# Smart_System.net
KiCad netlist of a schematic drawn in EasyEDA Pro
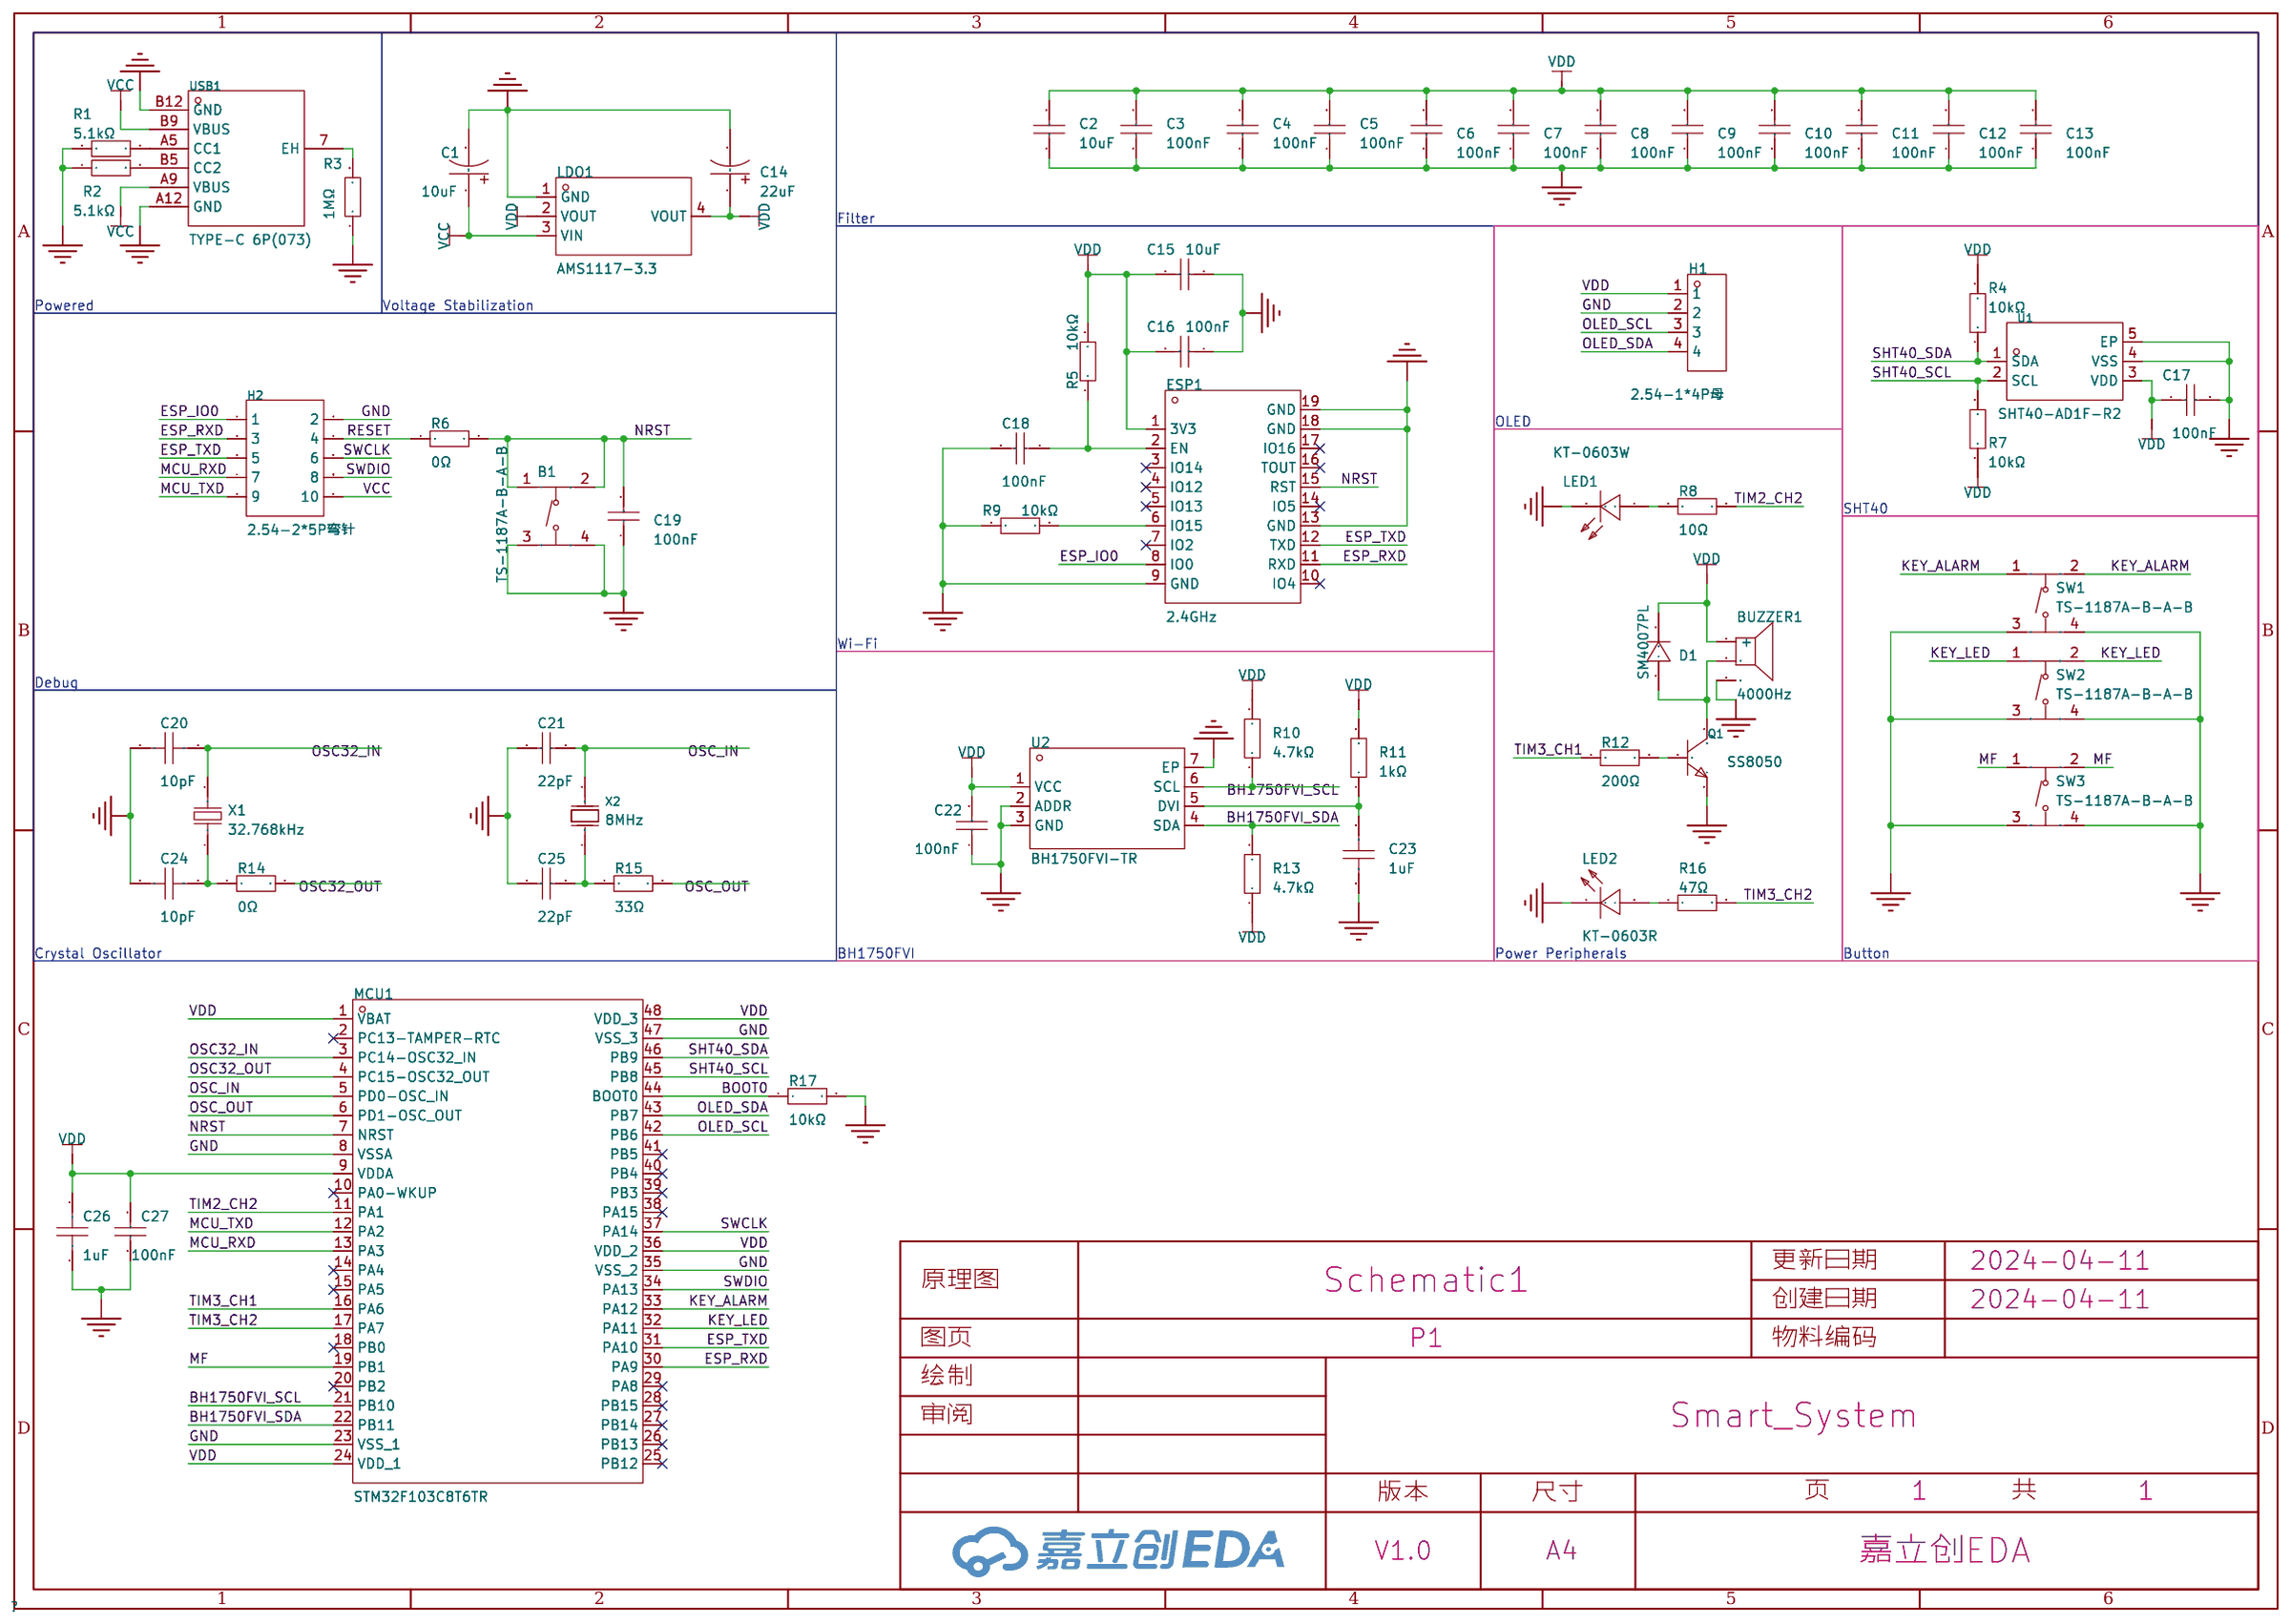
[diagram p0: schematic sheet]

(export (version "E")
  (design (tool "Eeschema 10.0.6"))
  (components
    (comp (ref "B1")
      (value "TS-1187A-B-A-B")
      (footprint "easyedapro:SW-SMD_4P-L5.1-W5.1-P3.70-LS6.5-TL-2")
      (description "触点电流:50mA;额定电压(DC):12V;绝缘电阻:-;电路结构:单刀单掷;安装方式:立贴;带灯:无;作用力:160gf;机械寿命:10万次;带支架:否;")
      (fields (field (name "Manufacturer") "XKB Connectivity(中国星坤)"))
      (libsource (lib "easyedapro") (part "TS-1187A-B-A-B"))
    )
    (comp (ref "BUZZER1")
      (value "4000Hz")
      (footprint "easyedapro:BUZ-SMD_FST-5018")
      (fields (field (name "Manufacturer Part") "FUET-5018") (field (name "Manufacturer") "FUET(福声科技)"))
      (libsource (lib "easyedapro") (part "FST-5018"))
    )
    (comp (ref "C1")
      (value "10uF")
      (footprint "easyedapro:CAP-SMD_BD3.0-L3.3-W3.3-FD")
      (description "容值:10uF;精度:±20%;额定电压:16V;纹波电流:-;等效串联电阻:-;")
      (fields (field (name "Manufacturer Part") "VE-100M1CTR-0305") (field (name "Manufacturer") "lelon(立隆)"))
      (libsource (lib "easyedapro") (part "VE-100M1C0305-TRO"))
    )
    (comp (ref "C2")
      (value "10uF")
      (footprint "easyedapro:C0402")
      (description "容值:10uF;精度:±20%;额定电压:6.3V;材质(温度系数):X5R;")
      (fields
        (field (name "Manufacturer Part") "CL05A106MQ5NUNC")
        (field (name "Manufacturer") "SAMSUNG(三星)")
      )
      (libsource (lib "easyedapro") (part "CL05A106MQ5NUNC"))
    )
    (comp (ref "C3")
      (value "100nF")
      (footprint "easyedapro:C0402")
      (description "容值:100nF;精度:±10%;额定电压:16V;材质(温度系数):X7R;")
      (fields
        (field (name "Manufacturer Part") "CL05B104KO5NNNC")
        (field (name "Manufacturer") "SAMSUNG(三星)")
      )
      (libsource (lib "easyedapro") (part "CL05B104KO5NNNC"))
    )
    (comp (ref "C4")
      (value "100nF")
      (footprint "easyedapro:C0402")
      (description "容值:100nF;精度:±10%;额定电压:16V;材质(温度系数):X7R;")
      (fields
        (field (name "Manufacturer Part") "CL05B104KO5NNNC")
        (field (name "Manufacturer") "SAMSUNG(三星)")
      )
      (libsource (lib "easyedapro") (part "CL05B104KO5NNNC"))
    )
    (comp (ref "C5")
      (value "100nF")
      (footprint "easyedapro:C0402")
      (description "容值:100nF;精度:±10%;额定电压:16V;材质(温度系数):X7R;")
      (fields
        (field (name "Manufacturer Part") "CL05B104KO5NNNC")
        (field (name "Manufacturer") "SAMSUNG(三星)")
      )
      (libsource (lib "easyedapro") (part "CL05B104KO5NNNC"))
    )
    (comp (ref "C6")
      (value "100nF")
      (footprint "easyedapro:C0402")
      (description "容值:100nF;精度:±10%;额定电压:16V;材质(温度系数):X7R;")
      (fields
        (field (name "Manufacturer Part") "CL05B104KO5NNNC")
        (field (name "Manufacturer") "SAMSUNG(三星)")
      )
      (libsource (lib "easyedapro") (part "CL05B104KO5NNNC"))
    )
    (comp (ref "C7")
      (value "100nF")
      (footprint "easyedapro:C0402")
      (description "容值:100nF;精度:±10%;额定电压:16V;材质(温度系数):X7R;")
      (fields
        (field (name "Manufacturer Part") "CL05B104KO5NNNC")
        (field (name "Manufacturer") "SAMSUNG(三星)")
      )
      (libsource (lib "easyedapro") (part "CL05B104KO5NNNC"))
    )
    (comp (ref "C8")
      (value "100nF")
      (footprint "easyedapro:C0402")
      (description "容值:100nF;精度:±10%;额定电压:16V;材质(温度系数):X7R;")
      (fields
        (field (name "Manufacturer Part") "CL05B104KO5NNNC")
        (field (name "Manufacturer") "SAMSUNG(三星)")
      )
      (libsource (lib "easyedapro") (part "CL05B104KO5NNNC"))
    )
    (comp (ref "C9")
      (value "100nF")
      (footprint "easyedapro:C0402")
      (description "容值:100nF;精度:±10%;额定电压:16V;材质(温度系数):X7R;")
      (fields
        (field (name "Manufacturer Part") "CL05B104KO5NNNC")
        (field (name "Manufacturer") "SAMSUNG(三星)")
      )
      (libsource (lib "easyedapro") (part "CL05B104KO5NNNC"))
    )
    (comp (ref "C10")
      (value "100nF")
      (footprint "easyedapro:C0402")
      (description "容值:100nF;精度:±10%;额定电压:16V;材质(温度系数):X7R;")
      (fields
        (field (name "Manufacturer Part") "CL05B104KO5NNNC")
        (field (name "Manufacturer") "SAMSUNG(三星)")
      )
      (libsource (lib "easyedapro") (part "CL05B104KO5NNNC"))
    )
    (comp (ref "C11")
      (value "100nF")
      (footprint "easyedapro:C0402")
      (description "容值:100nF;精度:±10%;额定电压:16V;材质(温度系数):X7R;")
      (fields
        (field (name "Manufacturer Part") "CL05B104KO5NNNC")
        (field (name "Manufacturer") "SAMSUNG(三星)")
      )
      (libsource (lib "easyedapro") (part "CL05B104KO5NNNC"))
    )
    (comp (ref "C12")
      (value "100nF")
      (footprint "easyedapro:C0402")
      (description "容值:100nF;精度:±10%;额定电压:16V;材质(温度系数):X7R;")
      (fields
        (field (name "Manufacturer Part") "CL05B104KO5NNNC")
        (field (name "Manufacturer") "SAMSUNG(三星)")
      )
      (libsource (lib "easyedapro") (part "CL05B104KO5NNNC"))
    )
    (comp (ref "C13")
      (value "100nF")
      (footprint "easyedapro:C0402")
      (description "容值:100nF;精度:±10%;额定电压:16V;材质(温度系数):X7R;")
      (fields
        (field (name "Manufacturer Part") "CL05B104KO5NNNC")
        (field (name "Manufacturer") "SAMSUNG(三星)")
      )
      (libsource (lib "easyedapro") (part "CL05B104KO5NNNC"))
    )
    (comp (ref "C14")
      (value "22uF")
      (footprint "easyedapro:CAP-SMD_BD3.0-L3.3-W3.3-FD")
      (description "容值:22uF;精度:±20%;额定电压:10V;纹波电流:-;等效串联电阻:-;")
      (fields (field (name "Manufacturer Part") "VE-220M1ATR-0305") (field (name "Manufacturer") "lelon(立隆)"))
      (libsource (lib "easyedapro") (part "VE-220M1A0305-TRO"))
    )
    (comp (ref "C15")
      (value "10uF")
      (footprint "easyedapro:C0402")
      (description "容值:10uF;精度:±20%;额定电压:6.3V;材质(温度系数):X5R;")
      (fields
        (field (name "Manufacturer Part") "CL05A106MQ5NUNC")
        (field (name "Manufacturer") "SAMSUNG(三星)")
      )
      (libsource (lib "easyedapro") (part "CL05A106MQ5NUNC"))
    )
    (comp (ref "C16")
      (value "100nF")
      (footprint "easyedapro:C0402")
      (description "容值:100nF;精度:±10%;额定电压:16V;材质(温度系数):X7R;")
      (fields
        (field (name "Manufacturer Part") "CL05B104KO5NNNC")
        (field (name "Manufacturer") "SAMSUNG(三星)")
      )
      (libsource (lib "easyedapro") (part "CL05B104KO5NNNC"))
    )
    (comp (ref "C17")
      (value "100nF")
      (footprint "easyedapro:C0402")
      (description "容值:100nF;精度:±10%;额定电压:16V;材质(温度系数):X7R;")
      (fields
        (field (name "Manufacturer Part") "CL05B104KO5NNNC")
        (field (name "Manufacturer") "SAMSUNG(三星)")
      )
      (libsource (lib "easyedapro") (part "CL05B104KO5NNNC"))
    )
    (comp (ref "C18")
      (value "100nF")
      (footprint "easyedapro:C0402")
      (description "容值:100nF;精度:±10%;额定电压:16V;材质(温度系数):X7R;")
      (fields
        (field (name "Manufacturer Part") "CL05B104KO5NNNC")
        (field (name "Manufacturer") "SAMSUNG(三星)")
      )
      (libsource (lib "easyedapro") (part "CL05B104KO5NNNC"))
    )
    (comp (ref "C19")
      (value "100nF")
      (footprint "easyedapro:C0402")
      (description "容值:100nF;精度:±10%;额定电压:16V;材质(温度系数):X7R;")
      (fields
        (field (name "Manufacturer Part") "CL05B104KO5NNNC")
        (field (name "Manufacturer") "SAMSUNG(三星)")
      )
      (libsource (lib "easyedapro") (part "CL05B104KO5NNNC"))
    )
    (comp (ref "C20")
      (value "10pF")
      (footprint "easyedapro:C0402")
      (description "容值:10pF;精度:±5%;额定电压:50V;材质(温度系数):C0G;")
      (fields
        (field (name "Manufacturer Part") "CL05C100JB5NNNC")
        (field (name "Manufacturer") "SAMSUNG(三星)")
      )
      (libsource (lib "easyedapro") (part "CL05C100JB5NNNC"))
    )
    (comp (ref "C21")
      (value "22pF")
      (footprint "easyedapro:C0402")
      (description "容值:22pF;精度:±5%;额定电压:50V;材质(温度系数):C0G;")
      (fields (field (name "Manufacturer Part") "0402CG220J500NT") (field (name "Manufacturer") "FH(风华)"))
      (libsource (lib "easyedapro") (part "0402CG220J500NT"))
    )
    (comp (ref "C22")
      (value "100nF")
      (footprint "easyedapro:C0402")
      (description "容值:100nF;精度:±10%;额定电压:16V;材质(温度系数):X7R;")
      (fields
        (field (name "Manufacturer Part") "CL05B104KO5NNNC")
        (field (name "Manufacturer") "SAMSUNG(三星)")
      )
      (libsource (lib "easyedapro") (part "CL05B104KO5NNNC"))
    )
    (comp (ref "C23")
      (value "1uF")
      (footprint "easyedapro:C0402")
      (description "容值:1uF;精度:±10%;额定电压:25V;材质(温度系数):X5R;")
      (fields
        (field (name "Manufacturer Part") "CL05A105KA5NQNC")
        (field (name "Manufacturer") "SAMSUNG(三星)")
      )
      (libsource (lib "easyedapro") (part "CL05A105KA5NQNC"))
    )
    (comp (ref "C24")
      (value "10pF")
      (footprint "easyedapro:C0402")
      (description "容值:10pF;精度:±5%;额定电压:50V;材质(温度系数):C0G;")
      (fields
        (field (name "Manufacturer Part") "CL05C100JB5NNNC")
        (field (name "Manufacturer") "SAMSUNG(三星)")
      )
      (libsource (lib "easyedapro") (part "CL05C100JB5NNNC"))
    )
    (comp (ref "C25")
      (value "22pF")
      (footprint "easyedapro:C0402")
      (description "容值:22pF;精度:±5%;额定电压:50V;材质(温度系数):C0G;")
      (fields (field (name "Manufacturer Part") "0402CG220J500NT") (field (name "Manufacturer") "FH(风华)"))
      (libsource (lib "easyedapro") (part "0402CG220J500NT"))
    )
    (comp (ref "C26")
      (value "1uF")
      (footprint "easyedapro:C0402")
      (description "容值:1uF;精度:±10%;额定电压:25V;材质(温度系数):X5R;")
      (fields
        (field (name "Manufacturer Part") "CL05A105KA5NQNC")
        (field (name "Manufacturer") "SAMSUNG(三星)")
      )
      (libsource (lib "easyedapro") (part "CL05A105KA5NQNC"))
    )
    (comp (ref "C27")
      (value "100nF")
      (footprint "easyedapro:C0402")
      (description "容值:100nF;精度:±10%;额定电压:16V;材质(温度系数):X7R;")
      (fields
        (field (name "Manufacturer Part") "CL05B104KO5NNNC")
        (field (name "Manufacturer") "SAMSUNG(三星)")
      )
      (libsource (lib "easyedapro") (part "CL05B104KO5NNNC"))
    )
    (comp (ref "D1")
      (value "SM4007PL")
      (footprint "easyedapro:SOD-123F_L2.8-W1.8-LS3.7-RD")
      (description "二极管配置:-;正向压降(Vf):1.1V@1A;直流反向耐压(Vr):1kV;平均整流电流(Io):1A;")
      (fields (field (name "Manufacturer") "MDD"))
      (libsource (lib "easyedapro") (part "SM4007PL"))
    )
    (comp (ref "ESP1")
      (value "2.4GHz")
      (footprint "easyedapro:WIFIM-SMD_18P-L18.0-W20.0-P1.50")
      (description "频率:2.4GHz;发射功率:20.5dBm;核心处理器:ESP8266EX;")
      (fields
        (field (name "Manufacturer Part") "ESP-WROOM-02-N4")
        (field (name "Manufacturer") "ESPRESSIF(乐鑫)")
      )
      (libsource (lib "easyedapro") (part "ESP-WROOM-02(4MB)"))
    )
    (comp (ref "H1")
      (value "2.54-1*4P母")
      (footprint "easyedapro:HDR-TH_4P-P2.54-V-F")
      (fields (field (name "Manufacturer") "BOOMELE(博穆精密)"))
      (libsource (lib "easyedapro") (part "2.54-1*4P母"))
    )
    (comp (ref "H2")
      (value "2.54-2*5P弯针")
      (footprint "easyedapro:HDR-TH_10P-P2.54-H-M-R2-C5-S2.54-W12.9")
      (fields (field (name "Manufacturer") "BOOMELE(博穆精密)"))
      (libsource (lib "easyedapro") (part "2*5P header"))
    )
    (comp (ref "LDO1")
      (value "AMS1117-3.3")
      (footprint "easyedapro:SOT-223-3_L6.5-W3.4-P2.30-LS7.0-BR")
      (description "输出类型:固定;输出极性:正;最大输入电压:-;输出电压:3.3V;输出电流:1A;电源纹波抑制比(PSRR):72dB@(120Hz);")
      (fields (field (name "Manufacturer") "AMS"))
      (libsource (lib "easyedapro") (part "AMS1117-3.3"))
    )
    (comp (ref "LED1")
      (value "KT-0603W")
      (footprint "easyedapro:LED0603-R-RD_WHITE")
      (description "发光颜色:白色;")
      (fields (field (name "Manufacturer") "KENTO"))
      (libsource (lib "easyedapro") (part "0603White light_C2290"))
    )
    (comp (ref "LED2")
      (value "KT-0603R")
      (footprint "easyedapro:LED0603-RD")
      (description "发光颜色:红灯;二极管配置:-;透镜颜色:-;主波长:-;色温:-;功率:-;发光角度:-;安装方式:-;工作温度:-40°C~+85°C;")
      (fields (field (name "Manufacturer") "KENTO"))
      (libsource (lib "easyedapro") (part "KT-0603R"))
    )
    (comp (ref "MCU1")
      (value "STM32F103C8T6TR")
      (footprint "easyedapro:LQFP-48_L7.0-W7.0-P0.50-LS9.0-BL")
      (fields (field (name "Manufacturer") "ST(意法半导体)"))
      (libsource (lib "easyedapro") (part "STM32F103C8T6TR"))
    )
    (comp (ref "Q1")
      (value "SS8050")
      (footprint "easyedapro:SOT-23-3_L2.9-W1.3-P1.90-LS2.4-BR")
      (description "晶体管类型:NPN;集射极击穿电压(Vceo):25V;集电极电流(Ic):1.5A;功率(Pd):300mW;直流电流增益(hFE@Ic,Vce):200@100mA,1V;")
      (fields (field (name "Manufacturer") "CJ(江苏长电/长晶)"))
      (libsource (lib "easyedapro") (part "SS8050_C2150"))
    )
    (comp (ref "R1")
      (value "5.1kΩ")
      (footprint "easyedapro:R0603")
      (description "阻值:5.1kΩ;精度:±1%;功率:100mW;温度系数:±100ppm/℃;电阻类型:厚膜电阻;")
      (fields
        (field (name "Manufacturer Part") "0603WAF5101T5E")
        (field (name "Manufacturer") "UNI-ROYAL(厚声)")
      )
      (libsource (lib "easyedapro") (part "0603WAF5101T5E"))
    )
    (comp (ref "R2")
      (value "5.1kΩ")
      (footprint "easyedapro:R0603")
      (description "阻值:5.1kΩ;精度:±1%;功率:100mW;温度系数:±100ppm/℃;电阻类型:厚膜电阻;")
      (fields
        (field (name "Manufacturer Part") "0603WAF5101T5E")
        (field (name "Manufacturer") "UNI-ROYAL(厚声)")
      )
      (libsource (lib "easyedapro") (part "0603WAF5101T5E"))
    )
    (comp (ref "R3")
      (value "1MΩ")
      (footprint "easyedapro:R0603")
      (description "阻值:1MΩ;精度:±1%;功率:100mW;温度系数:±100ppm/℃;电阻类型:厚膜电阻;")
      (fields
        (field (name "Manufacturer Part") "0603WAF1004T5E")
        (field (name "Manufacturer") "UNI-ROYAL(厚声)")
      )
      (libsource (lib "easyedapro") (part "0603WAF1004T5E"))
    )
    (comp (ref "R4")
      (value "10kΩ")
      (footprint "easyedapro:R0402")
      (description "电阻类型:厚膜电阻;阻值:10kΩ;精度:±1%;功率:62.5mW;温度系数:±100ppm/°C;")
      (fields
        (field (name "Manufacturer Part") "0402WGF1002TCE")
        (field (name "Manufacturer") "UNI-ROYAL(厚声)")
      )
      (libsource (lib "easyedapro") (part "0402WGF1002TCE"))
    )
    (comp (ref "R5")
      (value "10kΩ")
      (footprint "easyedapro:R0402")
      (description "电阻类型:厚膜电阻;阻值:10kΩ;精度:±1%;功率:62.5mW;温度系数:±100ppm/℃;")
      (fields
        (field (name "Manufacturer Part") "0402WGF1002TCE")
        (field (name "Manufacturer") "UNI-ROYAL(厚声)")
      )
      (libsource (lib "easyedapro") (part "0402WGF1002TCE"))
    )
    (comp (ref "R6")
      (value "0Ω")
      (footprint "easyedapro:R0402")
      (description "阻值:0Ω;精度:±1%;功率:62.5mW;温度系数:±800ppm/°C;电阻类型:厚膜电阻;")
      (fields
        (field (name "Manufacturer Part") "0402WGF0000TCE")
        (field (name "Manufacturer") "UNI-ROYAL(厚声)")
      )
      (libsource (lib "easyedapro") (part "0402WGF0000TCE"))
    )
    (comp (ref "R7")
      (value "10kΩ")
      (footprint "easyedapro:R0402")
      (description "电阻类型:厚膜电阻;阻值:10kΩ;精度:±1%;功率:62.5mW;温度系数:±100ppm/°C;")
      (fields
        (field (name "Manufacturer Part") "0402WGF1002TCE")
        (field (name "Manufacturer") "UNI-ROYAL(厚声)")
      )
      (libsource (lib "easyedapro") (part "0402WGF1002TCE"))
    )
    (comp (ref "R8")
      (value "10Ω")
      (footprint "easyedapro:R0402")
      (description "电阻类型:厚膜电阻;阻值:10Ω;精度:±1%;功率:62.5mW;最大工作电压:50V;温度系数:±200ppm/°C;")
      (fields
        (field (name "Manufacturer Part") "0402WGF100JTCE")
        (field (name "Manufacturer") "UNI-ROYAL(厚声)")
      )
      (libsource (lib "easyedapro") (part "0402WGF100JTCE"))
    )
    (comp (ref "R9")
      (value "10kΩ")
      (footprint "easyedapro:R0402")
      (description "电阻类型:厚膜电阻;阻值:10kΩ;精度:±1%;功率:62.5mW;温度系数:±100ppm/℃;")
      (fields
        (field (name "Manufacturer Part") "0402WGF1002TCE")
        (field (name "Manufacturer") "UNI-ROYAL(厚声)")
      )
      (libsource (lib "easyedapro") (part "0402WGF1002TCE"))
    )
    (comp (ref "R10")
      (value "4.7kΩ")
      (footprint "easyedapro:R0402")
      (description "电阻类型:厚膜电阻;阻值:4.7kΩ;精度:±1%;功率:62.5mW;温度系数:±100ppm/°C;")
      (fields
        (field (name "Manufacturer Part") "0402WGF4701TCE")
        (field (name "Manufacturer") "UNI-ROYAL(厚声)")
      )
      (libsource (lib "easyedapro") (part "0402WGF4701TCE"))
    )
    (comp (ref "R11")
      (value "1kΩ")
      (footprint "easyedapro:R0402")
      (description "电阻类型:厚膜电阻;阻值:1kΩ;精度:±1%;功率:62.5mW;")
      (fields
        (field (name "Manufacturer Part") "0402WGF1001TCE")
        (field (name "Manufacturer") "UNI-ROYAL(厚声)")
      )
      (libsource (lib "easyedapro") (part "0402WGF1001TCE"))
    )
    (comp (ref "R12")
      (value "200Ω")
      (footprint "easyedapro:R0402")
      (description "阻值:200Ω;精度:±1%;功率:62.5mW;温度系数:±100ppm/℃;电阻类型:厚膜电阻;")
      (fields
        (field (name "Manufacturer Part") "0402WGF2000TCE")
        (field (name "Manufacturer") "UNI-ROYAL(厚声)")
      )
      (libsource (lib "easyedapro") (part "0402WGF2000TCE"))
    )
    (comp (ref "R13")
      (value "4.7kΩ")
      (footprint "easyedapro:R0402")
      (description "电阻类型:厚膜电阻;阻值:4.7kΩ;精度:±1%;功率:62.5mW;温度系数:±100ppm/°C;")
      (fields
        (field (name "Manufacturer Part") "0402WGF4701TCE")
        (field (name "Manufacturer") "UNI-ROYAL(厚声)")
      )
      (libsource (lib "easyedapro") (part "0402WGF4701TCE"))
    )
    (comp (ref "R14")
      (value "0Ω")
      (footprint "easyedapro:R0402")
      (description "阻值:0Ω;精度:±1%;功率:62.5mW;温度系数:±800ppm/°C;电阻类型:厚膜电阻;")
      (fields
        (field (name "Manufacturer Part") "0402WGF0000TCE")
        (field (name "Manufacturer") "UNI-ROYAL(厚声)")
      )
      (libsource (lib "easyedapro") (part "0402WGF0000TCE"))
    )
    (comp (ref "R15")
      (value "33Ω")
      (footprint "easyedapro:R0402")
      (description "阻值:33Ω;精度:±1%;功率:62.5mW;温度系数:±100ppm/°C;电阻类型:厚膜电阻;")
      (fields
        (field (name "Manufacturer Part") "0402WGF330JTCE")
        (field (name "Manufacturer") "UNI-ROYAL(厚声)")
      )
      (libsource (lib "easyedapro") (part "0402WGF330JTCE"))
    )
    (comp (ref "R16")
      (value "47Ω")
      (footprint "easyedapro:R0603")
      (description "阻值:47Ω;精度:±1%;功率:100mW;温度系数:±100ppm/°C;电阻类型:厚膜电阻;")
      (fields
        (field (name "Manufacturer Part") "0603WAF470JT5E")
        (field (name "Manufacturer") "UNI-ROYAL(厚声)")
      )
      (libsource (lib "easyedapro") (part "0603WAF470JT5E"))
    )
    (comp (ref "R17")
      (value "10kΩ")
      (footprint "easyedapro:R0402")
      (description "电阻类型:厚膜电阻;阻值:10kΩ;精度:±1%;功率:62.5mW;温度系数:±100ppm/°C;")
      (fields
        (field (name "Manufacturer Part") "0402WGF1002TCE")
        (field (name "Manufacturer") "UNI-ROYAL(厚声)")
      )
      (libsource (lib "easyedapro") (part "0402WGF1002TCE"))
    )
    (comp (ref "SW1")
      (value "TS-1187A-B-A-B")
      (footprint "easyedapro:SW-SMD_4P-L5.1-W5.1-P3.70-LS6.5-TL-2")
      (description "触点电流:50mA;额定电压(DC):12V;绝缘电阻:-;电路结构:单刀单掷;安装方式:立贴;带灯:无;作用力:160gf;机械寿命:10万次;带支架:否;")
      (fields (field (name "Manufacturer") "XKB Connectivity(中国星坤)"))
      (libsource (lib "easyedapro") (part "TS-1187A-B-A-B"))
    )
    (comp (ref "SW2")
      (value "TS-1187A-B-A-B")
      (footprint "easyedapro:SW-SMD_4P-L5.1-W5.1-P3.70-LS6.5-TL-2")
      (description "触点电流:50mA;额定电压(DC):12V;绝缘电阻:-;电路结构:单刀单掷;安装方式:立贴;带灯:无;作用力:160gf;机械寿命:10万次;带支架:否;")
      (fields (field (name "Manufacturer") "XKB Connectivity(中国星坤)"))
      (libsource (lib "easyedapro") (part "TS-1187A-B-A-B"))
    )
    (comp (ref "SW3")
      (value "TS-1187A-B-A-B")
      (footprint "easyedapro:SW-SMD_4P-L5.1-W5.1-P3.70-LS6.5-TL-2")
      (description "触点电流:50mA;额定电压(DC):12V;绝缘电阻:-;电路结构:单刀单掷;安装方式:立贴;带灯:无;作用力:160gf;机械寿命:10万次;带支架:否;")
      (fields (field (name "Manufacturer") "XKB Connectivity(中国星坤)"))
      (libsource (lib "easyedapro") (part "TS-1187A-B-A-B"))
    )
    (comp (ref "U1")
      (value "SHT40-AD1F-R2")
      (footprint "easyedapro:DFN-4_L1.5-W1.5-P0.80-TL-EP")
      (fields (field (name "Manufacturer") "Sensirion(瑞士盛思锐)"))
      (libsource (lib "easyedapro") (part "SHT40-AD1F-R2"))
    )
    (comp (ref "U2")
      (value "BH1750FVI-TR")
      (footprint "easyedapro:WSOF-6_L2.6-W1.6-P0.50-TL-EP")
      (description "数字16-bit I2C串行输出，环境光传感器，工作电压：2.4V~3.6V")
      (fields (field (name "Manufacturer") "ROHM(罗姆)"))
      (libsource (lib "easyedapro") (part "BH1750FVI-TR"))
    )
    (comp (ref "USB1")
      (value "TYPE-C 6P(073)")
      (footprint "easyedapro:TYPE-C-SMD_TYPE-C-6P")
      (description "连接器类型:Type-C;标准:-;公母:母座;触点数量:6P;端口数量:1;安装方式:卧贴;额定电流 - 电源:5A;工作温度范围:-25°C~+85°C;")
      (fields (field (name "Manufacturer") "SHOU HAN(首韩)"))
      (libsource (lib "easyedapro") (part "TYPE-C 6P(073)"))
    )
    (comp (ref "X1")
      (value "32.768kHz")
      (footprint "easyedapro:FC-135R_L3.2-W1.5")
      (description "频率:32.768kHz;频率公差:±20ppm;负载电容:12.5pF;")
      (fields (field (name "Manufacturer Part") "Q13FC1350000400") (field (name "Manufacturer") "EPSON(爱普生)"))
      (libsource (lib "easyedapro") (part "Q13FC1350000400"))
    )
    (comp (ref "X2")
      (value "8MHz")
      (footprint "easyedapro:CRYSTAL-SMD_L5.0-W3.2")
      (description "频率:8MHz;负载电容:20pF;频率公差:±10ppm;")
      (fields (field (name "Manufacturer Part") "X50328MSB2GI") (field (name "Manufacturer") "YXC(扬兴晶振)"))
      (libsource (lib "easyedapro") (part "X50328MSB2GI"))
    )
  )
  (nets
    (net (code "1") (name "/BH1750FVI_SCL") (class "Default")
      (node (ref "MCU1") (pin "21") (pinfunction "PB10_21") (pintype "input"))
      (node (ref "R10") (pin "1") (pinfunction "1_1") (pintype "input"))
      (node (ref "U2") (pin "6") (pinfunction "SCL_6") (pintype "unspecified"))
    )
    (net (code "2") (name "/BH1750FVI_SDA") (class "Default")
      (node (ref "MCU1") (pin "22") (pinfunction "PB11_22") (pintype "input"))
      (node (ref "R13") (pin "2") (pinfunction "2_2") (pintype "input"))
      (node (ref "U2") (pin "4") (pinfunction "SDA_4") (pintype "unspecified"))
    )
    (net (code "3") (name "/BOOT0") (class "Default")
      (node (ref "MCU1") (pin "44") (pinfunction "BOOT0_44") (pintype "input"))
      (node (ref "R17") (pin "1") (pinfunction "1_1") (pintype "input"))
    )
    (net (code "4") (name "/ESP_IO0") (class "Default")
      (node (ref "ESP1") (pin "8") (pinfunction "IO0_8") (pintype "unspecified"))
      (node (ref "H2") (pin "1") (pinfunction "1_1") (pintype "input"))
    )
    (net (code "5") (name "/ESP_RXD") (class "Default")
      (node (ref "ESP1") (pin "11") (pinfunction "RXD_11") (pintype "unspecified"))
      (node (ref "H2") (pin "3") (pinfunction "3_3") (pintype "input"))
      (node (ref "MCU1") (pin "30") (pinfunction "PA9_30") (pintype "input"))
    )
    (net (code "6") (name "/ESP_TXD") (class "Default")
      (node (ref "ESP1") (pin "12") (pinfunction "TXD_12") (pintype "unspecified"))
      (node (ref "H2") (pin "5") (pinfunction "5_5") (pintype "input"))
      (node (ref "MCU1") (pin "31") (pinfunction "PA10_31") (pintype "input"))
    )
    (net (code "7") (name "/KEY_ALARM") (class "Default")
      (node (ref "MCU1") (pin "33") (pinfunction "PA12_33") (pintype "input"))
      (node (ref "SW1") (pin "1") (pinfunction "A_1") (pintype "input"))
      (node (ref "SW1") (pin "2") (pinfunction "B_2") (pintype "input"))
    )
    (net (code "8") (name "/KEY_LED") (class "Default")
      (node (ref "MCU1") (pin "32") (pinfunction "PA11_32") (pintype "input"))
      (node (ref "SW2") (pin "1") (pinfunction "A_1") (pintype "input"))
      (node (ref "SW2") (pin "2") (pinfunction "B_2") (pintype "input"))
    )
    (net (code "9") (name "/MCU_RXD") (class "Default")
      (node (ref "H2") (pin "7") (pinfunction "7_7") (pintype "input"))
      (node (ref "MCU1") (pin "13") (pinfunction "PA3_13") (pintype "input"))
    )
    (net (code "10") (name "/MCU_TXD") (class "Default")
      (node (ref "H2") (pin "9") (pinfunction "9_9") (pintype "input"))
      (node (ref "MCU1") (pin "12") (pinfunction "PA2_12") (pintype "input"))
    )
    (net (code "11") (name "/MF") (class "Default")
      (node (ref "MCU1") (pin "19") (pinfunction "PB1_19") (pintype "input"))
      (node (ref "SW3") (pin "1") (pinfunction "A_1") (pintype "input"))
      (node (ref "SW3") (pin "2") (pinfunction "B_2") (pintype "input"))
    )
    (net (code "12") (name "/NRST") (class "Default")
      (node (ref "B1") (pin "1") (pinfunction "A_1") (pintype "input"))
      (node (ref "B1") (pin "2") (pinfunction "B_2") (pintype "input"))
      (node (ref "C19") (pin "2") (pinfunction "2_2") (pintype "input"))
      (node (ref "ESP1") (pin "15") (pinfunction "RST_15") (pintype "unspecified"))
      (node (ref "MCU1") (pin "7") (pinfunction "NRST_7") (pintype "input"))
      (node (ref "R6") (pin "2") (pinfunction "2_2") (pintype "input"))
    )
    (net (code "13") (name "/OLED_SCL") (class "Default")
      (node (ref "H1") (pin "3") (pinfunction "3_3") (pintype "unspecified"))
      (node (ref "MCU1") (pin "42") (pinfunction "PB6_42") (pintype "input"))
    )
    (net (code "14") (name "/OLED_SDA") (class "Default")
      (node (ref "H1") (pin "4") (pinfunction "4_4") (pintype "unspecified"))
      (node (ref "MCU1") (pin "43") (pinfunction "PB7_43") (pintype "input"))
    )
    (net (code "15") (name "/OSC32_IN") (class "Default")
      (node (ref "C20") (pin "2") (pinfunction "2_2") (pintype "unspecified"))
      (node (ref "MCU1") (pin "3") (pinfunction "PC14-OSC32_IN_3") (pintype "input"))
      (node (ref "X1") (pin "2") (pinfunction "2_2") (pintype "unspecified"))
    )
    (net (code "16") (name "/OSC32_OUT") (class "Default")
      (node (ref "MCU1") (pin "4") (pinfunction "PC15-OSC32_OUT_4") (pintype "input"))
      (node (ref "R14") (pin "2") (pinfunction "2_2") (pintype "input"))
    )
    (net (code "17") (name "/OSC_IN") (class "Default")
      (node (ref "C21") (pin "2") (pinfunction "2_2") (pintype "input"))
      (node (ref "MCU1") (pin "5") (pinfunction "PD0-OSC_IN_5") (pintype "input"))
      (node (ref "X2") (pin "2") (pinfunction "OSC2_2") (pintype "input"))
    )
    (net (code "18") (name "/OSC_OUT") (class "Default")
      (node (ref "MCU1") (pin "6") (pinfunction "PD1-OSC_OUT_6") (pintype "input"))
      (node (ref "R15") (pin "2") (pinfunction "2_2") (pintype "input"))
    )
    (net (code "19") (name "/RESET") (class "Default")
      (node (ref "H2") (pin "4") (pinfunction "4_4") (pintype "input"))
      (node (ref "R6") (pin "1") (pinfunction "1_1") (pintype "input"))
    )
    (net (code "20") (name "/SHT40_SCL") (class "Default")
      (node (ref "MCU1") (pin "45") (pinfunction "PB8_45") (pintype "input"))
      (node (ref "R7") (pin "2") (pinfunction "2_2") (pintype "input"))
      (node (ref "U1") (pin "2") (pinfunction "SCL_2") (pintype "input"))
    )
    (net (code "21") (name "/SHT40_SDA") (class "Default")
      (node (ref "MCU1") (pin "46") (pinfunction "PB9_46") (pintype "input"))
      (node (ref "R4") (pin "1") (pinfunction "1_1") (pintype "input"))
      (node (ref "U1") (pin "1") (pinfunction "SDA_1") (pintype "input"))
    )
    (net (code "22") (name "/SWCLK") (class "Default")
      (node (ref "H2") (pin "6") (pinfunction "6_6") (pintype "input"))
      (node (ref "MCU1") (pin "37") (pinfunction "PA14_37") (pintype "input"))
    )
    (net (code "23") (name "/SWDIO") (class "Default")
      (node (ref "H2") (pin "8") (pinfunction "8_8") (pintype "input"))
      (node (ref "MCU1") (pin "34") (pinfunction "PA13_34") (pintype "input"))
    )
    (net (code "24") (name "/TIM2_CH2") (class "Default")
      (node (ref "MCU1") (pin "11") (pinfunction "PA1_11") (pintype "input"))
      (node (ref "R8") (pin "1") (pinfunction "1_1") (pintype "input"))
    )
    (net (code "25") (name "/TIM3_CH1") (class "Default")
      (node (ref "MCU1") (pin "16") (pinfunction "PA6_16") (pintype "input"))
      (node (ref "R12") (pin "1") (pinfunction "1_1") (pintype "input"))
    )
    (net (code "26") (name "/TIM3_CH2") (class "Default")
      (node (ref "MCU1") (pin "17") (pinfunction "PA7_17") (pintype "input"))
      (node (ref "R16") (pin "2") (pinfunction "2_2") (pintype "input"))
    )
    (net (code "27") (name "GND") (class "Default")
      (node (ref "B1") (pin "3") (pinfunction "C_3") (pintype "input"))
      (node (ref "B1") (pin "4") (pinfunction "D_4") (pintype "input"))
      (node (ref "BUZZER1") (pin "3") (pinfunction "3_3") (pintype "input"))
      (node (ref "C1") (pin "2") (pinfunction "2_2") (pintype "input"))
      (node (ref "C10") (pin "1") (pinfunction "1_1") (pintype "input"))
      (node (ref "C11") (pin "1") (pinfunction "1_1") (pintype "input"))
      (node (ref "C12") (pin "1") (pinfunction "1_1") (pintype "input"))
      (node (ref "C13") (pin "1") (pinfunction "1_1") (pintype "input"))
      (node (ref "C14") (pin "2") (pinfunction "2_2") (pintype "input"))
      (node (ref "C15") (pin "2") (pinfunction "2_2") (pintype "input"))
      (node (ref "C16") (pin "1") (pinfunction "1_1") (pintype "input"))
      (node (ref "C17") (pin "2") (pinfunction "2_2") (pintype "input"))
      (node (ref "C18") (pin "2") (pinfunction "2_2") (pintype "input"))
      (node (ref "C19") (pin "1") (pinfunction "1_1") (pintype "input"))
      (node (ref "C2") (pin "1") (pinfunction "1_1") (pintype "input"))
      (node (ref "C20") (pin "1") (pinfunction "1_1") (pintype "unspecified"))
      (node (ref "C21") (pin "1") (pinfunction "1_1") (pintype "input"))
      (node (ref "C22") (pin "1") (pinfunction "1_1") (pintype "input"))
      (node (ref "C23") (pin "1") (pinfunction "1_1") (pintype "unspecified"))
      (node (ref "C24") (pin "1") (pinfunction "1_1") (pintype "unspecified"))
      (node (ref "C25") (pin "1") (pinfunction "1_1") (pintype "input"))
      (node (ref "C26") (pin "1") (pinfunction "1_1") (pintype "unspecified"))
      (node (ref "C27") (pin "1") (pinfunction "1_1") (pintype "input"))
      (node (ref "C3") (pin "1") (pinfunction "1_1") (pintype "input"))
      (node (ref "C4") (pin "1") (pinfunction "1_1") (pintype "input"))
      (node (ref "C5") (pin "1") (pinfunction "1_1") (pintype "input"))
      (node (ref "C6") (pin "1") (pinfunction "1_1") (pintype "input"))
      (node (ref "C7") (pin "1") (pinfunction "1_1") (pintype "input"))
      (node (ref "C8") (pin "1") (pinfunction "1_1") (pintype "input"))
      (node (ref "C9") (pin "1") (pinfunction "1_1") (pintype "input"))
      (node (ref "ESP1") (pin "13") (pinfunction "GND_13") (pintype "unspecified"))
      (node (ref "ESP1") (pin "18") (pinfunction "GND_18") (pintype "unspecified"))
      (node (ref "ESP1") (pin "19") (pinfunction "GND_19") (pintype "unspecified"))
      (node (ref "ESP1") (pin "9") (pinfunction "GND_9") (pintype "unspecified"))
      (node (ref "H1") (pin "2") (pinfunction "2_2") (pintype "unspecified"))
      (node (ref "H2") (pin "2") (pinfunction "2_2") (pintype "input"))
      (node (ref "LDO1") (pin "1") (pinfunction "GND_1") (pintype "unspecified"))
      (node (ref "LED1") (pin "2") (pinfunction "K_2") (pintype "unspecified"))
      (node (ref "LED2") (pin "1") (pinfunction "K_1") (pintype "input"))
      (node (ref "MCU1") (pin "23") (pinfunction "VSS_1_23") (pintype "input"))
      (node (ref "MCU1") (pin "35") (pinfunction "VSS_2_35") (pintype "input"))
      (node (ref "MCU1") (pin "47") (pinfunction "VSS_3_47") (pintype "input"))
      (node (ref "MCU1") (pin "8") (pinfunction "VSSA_8") (pintype "input"))
      (node (ref "Q1") (pin "2") (pinfunction "E_2") (pintype "unspecified"))
      (node (ref "R1") (pin "1") (pinfunction "1_1") (pintype "input"))
      (node (ref "R17") (pin "2") (pinfunction "2_2") (pintype "input"))
      (node (ref "R2") (pin "1") (pinfunction "1_1") (pintype "input"))
      (node (ref "R3") (pin "1") (pinfunction "1_1") (pintype "input"))
      (node (ref "R9") (pin "1") (pinfunction "1_1") (pintype "input"))
      (node (ref "SW1") (pin "3") (pinfunction "C_3") (pintype "input"))
      (node (ref "SW1") (pin "4") (pinfunction "D_4") (pintype "input"))
      (node (ref "SW2") (pin "3") (pinfunction "C_3") (pintype "input"))
      (node (ref "SW2") (pin "4") (pinfunction "D_4") (pintype "input"))
      (node (ref "SW3") (pin "3") (pinfunction "C_3") (pintype "input"))
      (node (ref "SW3") (pin "4") (pinfunction "D_4") (pintype "input"))
      (node (ref "U1") (pin "4") (pinfunction "VSS_4") (pintype "input"))
      (node (ref "U1") (pin "5") (pinfunction "EP_5") (pintype "input"))
      (node (ref "U2") (pin "2") (pinfunction "ADDR_2") (pintype "unspecified"))
      (node (ref "U2") (pin "3") (pinfunction "GND_3") (pintype "unspecified"))
      (node (ref "U2") (pin "7") (pinfunction "EP_7") (pintype "unspecified"))
      (node (ref "USB1") (pin "A12") (pinfunction "GND_A12") (pintype "unspecified"))
      (node (ref "USB1") (pin "B12") (pinfunction "GND_B12") (pintype "unspecified"))
    )
    (net (code "28") (name "Net-(C24-Pad2)") (class "Default")
      (node (ref "C24") (pin "2") (pinfunction "2_2") (pintype "unspecified"))
      (node (ref "R14") (pin "1") (pinfunction "1_1") (pintype "input"))
      (node (ref "X1") (pin "1") (pinfunction "1_1") (pintype "unspecified"))
    )
    (net (code "29") (name "Net-(D1-A)") (class "Default")
      (node (ref "BUZZER1") (pin "2") (pinfunction "2_2") (pintype "input"))
      (node (ref "D1") (pin "2") (pinfunction "A_2") (pintype "unspecified"))
      (node (ref "Q1") (pin "3") (pinfunction "C_3") (pintype "unspecified"))
    )
    (net (code "30") (name "Net-(ESP1-EN)") (class "Default")
      (node (ref "C18") (pin "1") (pinfunction "1_1") (pintype "input"))
      (node (ref "ESP1") (pin "2") (pinfunction "EN_2") (pintype "unspecified"))
      (node (ref "R5") (pin "1") (pinfunction "1_1") (pintype "input"))
    )
    (net (code "31") (name "Net-(ESP1-IO15)") (class "Default")
      (node (ref "ESP1") (pin "6") (pinfunction "IO15_6") (pintype "unspecified"))
      (node (ref "R9") (pin "2") (pinfunction "2_2") (pintype "input"))
    )
    (net (code "32") (name "Net-(LED1-A)") (class "Default")
      (node (ref "LED1") (pin "1") (pinfunction "A_1") (pintype "unspecified"))
      (node (ref "R8") (pin "2") (pinfunction "2_2") (pintype "input"))
    )
    (net (code "33") (name "Net-(LED2-A)") (class "Default")
      (node (ref "LED2") (pin "2") (pinfunction "A_2") (pintype "input"))
      (node (ref "R16") (pin "1") (pinfunction "1_1") (pintype "input"))
    )
    (net (code "34") (name "Net-(Q1-B)") (class "Default")
      (node (ref "Q1") (pin "1") (pinfunction "B_1") (pintype "unspecified"))
      (node (ref "R12") (pin "2") (pinfunction "2_2") (pintype "input"))
    )
    (net (code "35") (name "Net-(U2-DVI)") (class "Default")
      (node (ref "C23") (pin "2") (pinfunction "2_2") (pintype "unspecified"))
      (node (ref "R11") (pin "1") (pinfunction "1_1") (pintype "input"))
      (node (ref "U2") (pin "5") (pinfunction "DVI_5") (pintype "unspecified"))
    )
    (net (code "36") (name "Net-(USB1-CC1)") (class "Default")
      (node (ref "R1") (pin "2") (pinfunction "2_2") (pintype "input"))
      (node (ref "USB1") (pin "A5") (pinfunction "CC1_A5") (pintype "unspecified"))
    )
    (net (code "37") (name "Net-(USB1-CC2)") (class "Default")
      (node (ref "R2") (pin "2") (pinfunction "2_2") (pintype "input"))
      (node (ref "USB1") (pin "B5") (pinfunction "CC2_B5") (pintype "unspecified"))
    )
    (net (code "38") (name "Net-(USB1-EH)") (class "Default")
      (node (ref "R3") (pin "2") (pinfunction "2_2") (pintype "input"))
      (node (ref "USB1") (pin "7") (pinfunction "EH_7") (pintype "unspecified"))
    )
    (net (code "39") (name "Net-(X2-OSC1)") (class "Default")
      (node (ref "C25") (pin "2") (pinfunction "2_2") (pintype "input"))
      (node (ref "R15") (pin "1") (pinfunction "1_1") (pintype "input"))
      (node (ref "X2") (pin "1") (pinfunction "OSC1_1") (pintype "input"))
    )
    (net (code "40") (name "VCC") (class "Default")
      (node (ref "C1") (pin "1") (pinfunction "1_1") (pintype "input"))
      (node (ref "H2") (pin "10") (pinfunction "10_10") (pintype "input"))
      (node (ref "LDO1") (pin "3") (pinfunction "VIN_3") (pintype "unspecified"))
      (node (ref "USB1") (pin "A9") (pinfunction "VBUS_A9") (pintype "unspecified"))
      (node (ref "USB1") (pin "B9") (pinfunction "VBUS_B9") (pintype "unspecified"))
    )
    (net (code "41") (name "VDD") (class "Default")
      (node (ref "BUZZER1") (pin "1") (pinfunction "+_1") (pintype "input"))
      (node (ref "C10") (pin "2") (pinfunction "2_2") (pintype "input"))
      (node (ref "C11") (pin "2") (pinfunction "2_2") (pintype "input"))
      (node (ref "C12") (pin "2") (pinfunction "2_2") (pintype "input"))
      (node (ref "C13") (pin "2") (pinfunction "2_2") (pintype "input"))
      (node (ref "C14") (pin "1") (pinfunction "1_1") (pintype "input"))
      (node (ref "C15") (pin "1") (pinfunction "1_1") (pintype "input"))
      (node (ref "C16") (pin "2") (pinfunction "2_2") (pintype "input"))
      (node (ref "C17") (pin "1") (pinfunction "1_1") (pintype "input"))
      (node (ref "C2") (pin "2") (pinfunction "2_2") (pintype "input"))
      (node (ref "C22") (pin "2") (pinfunction "2_2") (pintype "input"))
      (node (ref "C26") (pin "2") (pinfunction "2_2") (pintype "unspecified"))
      (node (ref "C27") (pin "2") (pinfunction "2_2") (pintype "input"))
      (node (ref "C3") (pin "2") (pinfunction "2_2") (pintype "input"))
      (node (ref "C4") (pin "2") (pinfunction "2_2") (pintype "input"))
      (node (ref "C5") (pin "2") (pinfunction "2_2") (pintype "input"))
      (node (ref "C6") (pin "2") (pinfunction "2_2") (pintype "input"))
      (node (ref "C7") (pin "2") (pinfunction "2_2") (pintype "input"))
      (node (ref "C8") (pin "2") (pinfunction "2_2") (pintype "input"))
      (node (ref "C9") (pin "2") (pinfunction "2_2") (pintype "input"))
      (node (ref "D1") (pin "1") (pinfunction "C_1") (pintype "unspecified"))
      (node (ref "ESP1") (pin "1") (pinfunction "3V3_1") (pintype "unspecified"))
      (node (ref "H1") (pin "1") (pinfunction "1_1") (pintype "unspecified"))
      (node (ref "LDO1") (pin "2") (pinfunction "VOUT_2") (pintype "unspecified"))
      (node (ref "LDO1") (pin "4") (pinfunction "VOUT_4") (pintype "unspecified"))
      (node (ref "MCU1") (pin "1") (pinfunction "VBAT_1") (pintype "input"))
      (node (ref "MCU1") (pin "24") (pinfunction "VDD_1_24") (pintype "input"))
      (node (ref "MCU1") (pin "36") (pinfunction "VDD_2_36") (pintype "input"))
      (node (ref "MCU1") (pin "48") (pinfunction "VDD_3_48") (pintype "input"))
      (node (ref "MCU1") (pin "9") (pinfunction "VDDA_9") (pintype "input"))
      (node (ref "R10") (pin "2") (pinfunction "2_2") (pintype "input"))
      (node (ref "R11") (pin "2") (pinfunction "2_2") (pintype "input"))
      (node (ref "R13") (pin "1") (pinfunction "1_1") (pintype "input"))
      (node (ref "R4") (pin "2") (pinfunction "2_2") (pintype "input"))
      (node (ref "R5") (pin "2") (pinfunction "2_2") (pintype "input"))
      (node (ref "R7") (pin "1") (pinfunction "1_1") (pintype "input"))
      (node (ref "U1") (pin "3") (pinfunction "VDD_3") (pintype "input"))
      (node (ref "U2") (pin "1") (pinfunction "VCC_1") (pintype "unspecified"))
    )
    (net (code "42") (name "unconnected-(ESP1-IO2-Pad7)") (class "Default")
      (node (ref "ESP1") (pin "7") (pinfunction "IO2_7") (pintype "unspecified+no_connect"))
    )
    (net (code "43") (name "unconnected-(ESP1-IO4-Pad10)") (class "Default")
      (node (ref "ESP1") (pin "10") (pinfunction "IO4_10") (pintype "unspecified+no_connect"))
    )
    (net (code "44") (name "unconnected-(ESP1-IO5-Pad14)") (class "Default")
      (node (ref "ESP1") (pin "14") (pinfunction "IO5_14") (pintype "unspecified+no_connect"))
    )
    (net (code "45") (name "unconnected-(ESP1-IO12-Pad4)") (class "Default")
      (node (ref "ESP1") (pin "4") (pinfunction "IO12_4") (pintype "unspecified+no_connect"))
    )
    (net (code "46") (name "unconnected-(ESP1-IO13-Pad5)") (class "Default")
      (node (ref "ESP1") (pin "5") (pinfunction "IO13_5") (pintype "unspecified+no_connect"))
    )
    (net (code "47") (name "unconnected-(ESP1-IO14-Pad3)") (class "Default")
      (node (ref "ESP1") (pin "3") (pinfunction "IO14_3") (pintype "unspecified+no_connect"))
    )
    (net (code "48") (name "unconnected-(ESP1-IO16-Pad17)") (class "Default")
      (node (ref "ESP1") (pin "17") (pinfunction "IO16_17") (pintype "unspecified+no_connect"))
    )
    (net (code "49") (name "unconnected-(ESP1-TOUT-Pad16)") (class "Default")
      (node (ref "ESP1") (pin "16") (pinfunction "TOUT_16") (pintype "unspecified+no_connect"))
    )
    (net (code "50") (name "unconnected-(MCU1-PA0-WKUP-Pad10)") (class "Default")
      (node (ref "MCU1") (pin "10") (pinfunction "PA0-WKUP_10") (pintype "input+no_connect"))
    )
    (net (code "51") (name "unconnected-(MCU1-PA4-Pad14)") (class "Default")
      (node (ref "MCU1") (pin "14") (pinfunction "PA4_14") (pintype "input+no_connect"))
    )
    (net (code "52") (name "unconnected-(MCU1-PA5-Pad15)") (class "Default")
      (node (ref "MCU1") (pin "15") (pinfunction "PA5_15") (pintype "input+no_connect"))
    )
    (net (code "53") (name "unconnected-(MCU1-PA8-Pad29)") (class "Default")
      (node (ref "MCU1") (pin "29") (pinfunction "PA8_29") (pintype "input+no_connect"))
    )
    (net (code "54") (name "unconnected-(MCU1-PA15-Pad38)") (class "Default")
      (node (ref "MCU1") (pin "38") (pinfunction "PA15_38") (pintype "input+no_connect"))
    )
    (net (code "55") (name "unconnected-(MCU1-PB0-Pad18)") (class "Default")
      (node (ref "MCU1") (pin "18") (pinfunction "PB0_18") (pintype "input+no_connect"))
    )
    (net (code "56") (name "unconnected-(MCU1-PB2-Pad20)") (class "Default")
      (node (ref "MCU1") (pin "20") (pinfunction "PB2_20") (pintype "input+no_connect"))
    )
    (net (code "57") (name "unconnected-(MCU1-PB3-Pad39)") (class "Default")
      (node (ref "MCU1") (pin "39") (pinfunction "PB3_39") (pintype "input+no_connect"))
    )
    (net (code "58") (name "unconnected-(MCU1-PB4-Pad40)") (class "Default")
      (node (ref "MCU1") (pin "40") (pinfunction "PB4_40") (pintype "input+no_connect"))
    )
    (net (code "59") (name "unconnected-(MCU1-PB5-Pad41)") (class "Default")
      (node (ref "MCU1") (pin "41") (pinfunction "PB5_41") (pintype "input+no_connect"))
    )
    (net (code "60") (name "unconnected-(MCU1-PB12-Pad25)") (class "Default")
      (node (ref "MCU1") (pin "25") (pinfunction "PB12_25") (pintype "input+no_connect"))
    )
    (net (code "61") (name "unconnected-(MCU1-PB13-Pad26)") (class "Default")
      (node (ref "MCU1") (pin "26") (pinfunction "PB13_26") (pintype "input+no_connect"))
    )
    (net (code "62") (name "unconnected-(MCU1-PB14-Pad27)") (class "Default")
      (node (ref "MCU1") (pin "27") (pinfunction "PB14_27") (pintype "input+no_connect"))
    )
    (net (code "63") (name "unconnected-(MCU1-PB15-Pad28)") (class "Default")
      (node (ref "MCU1") (pin "28") (pinfunction "PB15_28") (pintype "input+no_connect"))
    )
    (net (code "64") (name "unconnected-(MCU1-PC13-TAMPER-RTC-Pad2)") (class "Default")
      (node (ref "MCU1") (pin "2") (pinfunction "PC13-TAMPER-RTC_2") (pintype "input+no_connect"))
    )
  )
)
